# orienteringsklokke_v3.net
KiCad netlist of a schematic drawn in EAGLE
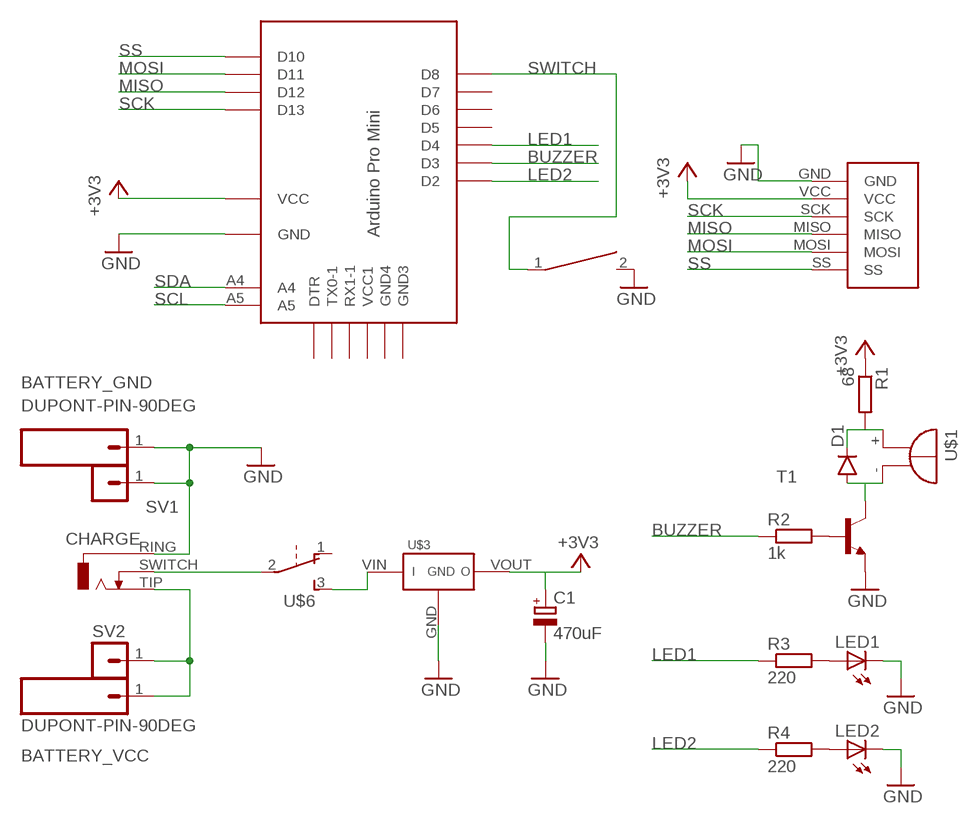
[diagram p0: schematic, sheet 1]

(export (version "E")
  (design (tool "Eeschema 10.0.6"))
  (components
    (comp (ref "BATTERY_GND")
      (value "DUPONT-PIN-90DEG")
      (footprint "eagle-import:DUPONT-PIN-90DEG")
      (libsource (lib "eagle-import") (part "DUPONT-PIN-90DEG"))
    )
    (comp (ref "BATTERY_VCC")
      (value "DUPONT-PIN-90DEG")
      (footprint "eagle-import:DUPONT-PIN-90DEG")
      (libsource (lib "eagle-import") (part "DUPONT-PIN-90DEG"))
    )
    (comp (ref "C1")
      (value "470uF")
      (footprint "eagle-import:CAP-HORIZ-6.5X11X2.5")
      (libsource (lib "eagle-import") (part "CAP-HORIZ"))
    )
    (comp (ref "CHARGE")
      (value "ST613-JACK")
      (footprint "eagle-import:ST613-JACK")
      (libsource (lib "eagle-import") (part "ST613-JACK"))
    )
    (comp (ref "D1")
      (value "1N4148DOJ35-5")
      (footprint "eagle-import:DO35-5J")
      (libsource (lib "eagle-import") (part "1N4148DOJ35-5"))
    )
    (comp (ref "LED1")
      (value "LED_J3MM-LEFT")
      (footprint "eagle-import:LED90DEG_LEFT")
      (libsource (lib "eagle-import") (part "LED_J3MM-LEFT"))
    )
    (comp (ref "LED2")
      (value "LED_J3MM-LEFT")
      (footprint "eagle-import:LED90DEG_LEFT")
      (libsource (lib "eagle-import") (part "LED_J3MM-LEFT"))
    )
    (comp (ref "R1")
      (value "68")
      (footprint "eagle-import:0204_5")
      (libsource (lib "eagle-import") (part "R-EU_0204/5"))
    )
    (comp (ref "R2")
      (value "1k")
      (footprint "eagle-import:0204_5")
      (libsource (lib "eagle-import") (part "R-EU_0204/5"))
    )
    (comp (ref "R3")
      (value "220")
      (footprint "eagle-import:0204_5")
      (libsource (lib "eagle-import") (part "R-EU_0204/5"))
    )
    (comp (ref "R4")
      (value "220")
      (footprint "eagle-import:0204_5")
      (libsource (lib "eagle-import") (part "R-EU_0204/5"))
    )
    (comp (ref "SV1")
      (value "MA01-1JC")
      (footprint "eagle-import:MA01-1J")
      (libsource (lib "eagle-import") (part "MA01-1JC"))
    )
    (comp (ref "SV2")
      (value "MA01-1JC")
      (footprint "eagle-import:MA01-1J")
      (libsource (lib "eagle-import") (part "MA01-1JC"))
    )
    (comp (ref "T1")
      (value "2N3904-NPN-TO92-EBC")
      (footprint "eagle-import:TO92-EBC")
      (libsource (lib "eagle-import") (part "-NPN-TO92-EBC2N3904"))
    )
    (comp (ref "U$1")
      (value "BUZZER_JL")
      (footprint "eagle-import:BUZZER_HORIZ_J_LEFT")
      (libsource (lib "eagle-import") (part "BUZZER_JL"))
    )
    (comp (ref "U$2")
      (value "NFC_MODULE_V3_SPINH")
      (footprint "eagle-import:NFC_MODULE_V3_SPI_CENTERED_NO_HOLES")
      (libsource (lib "eagle-import") (part "NFC_MODULE_V3_SPINH"))
    )
    (comp (ref "U$3")
      (value "VOLT_BOOST")
      (footprint "eagle-import:VOLT-BOOST")
      (libsource (lib "eagle-import") (part "VOLT_BOOST"))
    )
    (comp (ref "U$4")
      (value "ARD-PRO-MINI-ORIENTERING")
      (footprint "eagle-import:ARD_PRO_MINI_ORIENTERING")
      (libsource (lib "eagle-import") (part "ARD-PRO-MINI-ORIENTERING"))
    )
    (comp (ref "U$5")
      (value "PUSHBUTTON_2P6MM")
      (footprint "eagle-import:PUSHBUTTON_HORIZ_6MM_J")
      (libsource (lib "eagle-import") (part "PUSHBUTTON_2P6MM"))
    )
    (comp (ref "U$6")
      (value "SK12D07-SLIDE-SWITCH")
      (footprint "eagle-import:SK12D07")
      (libsource (lib "eagle-import") (part "SK12D07-SLIDE-SWITCH"))
    )
  )
  (nets
    (net (code "1") (name "+3V3") (class "Default")
      (node (ref "C1") (pin "+") (pinfunction "+_+") (pintype "passive"))
      (node (ref "R1") (pin "1") (pinfunction "1_1") (pintype "passive"))
      (node (ref "U$2") (pin "VCC") (pinfunction "VCC_VCC") (pintype "bidirectional"))
      (node (ref "U$3") (pin "VOUT") (pinfunction "VOUT_VOUT") (pintype "bidirectional"))
      (node (ref "U$4") (pin "VCC") (pinfunction "VCC_VCC") (pintype "bidirectional"))
    )
    (net (code "2") (name "BUZZER") (class "Default")
      (node (ref "R2") (pin "1") (pinfunction "1_1") (pintype "passive"))
      (node (ref "U$4") (pin "D3") (pinfunction "D3_D3") (pintype "bidirectional"))
    )
    (net (code "3") (name "GND") (class "Default")
      (node (ref "BATTERY_GND") (pin "1") (pinfunction "1_1") (pintype "passive"))
      (node (ref "C1") (pin "-") (pinfunction "-_-") (pintype "passive"))
      (node (ref "CHARGE") (pin "RING") (pinfunction "1_RING") (pintype "passive"))
      (node (ref "LED1") (pin "K") (pinfunction "C_K") (pintype "passive"))
      (node (ref "LED2") (pin "K") (pinfunction "C_K") (pintype "passive"))
      (node (ref "SV1") (pin "1") (pinfunction "1_1") (pintype "passive"))
      (node (ref "T1") (pin "E") (pinfunction "E_E") (pintype "passive"))
      (node (ref "U$2") (pin "GND") (pinfunction "GND_GND") (pintype "bidirectional"))
      (node (ref "U$3") (pin "GND") (pinfunction "GND_GND") (pintype "bidirectional"))
      (node (ref "U$4") (pin "GND") (pinfunction "GND_GND") (pintype "bidirectional"))
      (node (ref "U$5") (pin "2") (pinfunction "2_2") (pintype "bidirectional"))
    )
    (net (code "4") (name "LED1") (class "Default")
      (node (ref "R3") (pin "1") (pinfunction "1_1") (pintype "passive"))
      (node (ref "U$4") (pin "D4") (pinfunction "D4_D4") (pintype "bidirectional"))
    )
    (net (code "5") (name "LED2") (class "Default")
      (node (ref "R4") (pin "1") (pinfunction "1_1") (pintype "passive"))
      (node (ref "U$4") (pin "D2") (pinfunction "D2_D2") (pintype "bidirectional"))
    )
    (net (code "6") (name "MISO") (class "Default")
      (node (ref "U$2") (pin "MISO") (pinfunction "MISO_MISO") (pintype "bidirectional"))
      (node (ref "U$4") (pin "D12") (pinfunction "D12_D12") (pintype "bidirectional"))
    )
    (net (code "7") (name "MOSI") (class "Default")
      (node (ref "U$2") (pin "MOSI") (pinfunction "MOSI_MOSI") (pintype "bidirectional"))
      (node (ref "U$4") (pin "D11") (pinfunction "D11_D11") (pintype "bidirectional"))
    )
    (net (code "8") (name "Net-(CHARGE-2)") (class "Default")
      (node (ref "CHARGE") (pin "SWITCH") (pinfunction "2_SWITCH") (pintype "passive"))
      (node (ref "U$6") (pin "2") (pinfunction "2_2") (pintype "passive"))
    )
    (net (code "9") (name "Net-(CHARGE-3)") (class "Default")
      (node (ref "BATTERY_VCC") (pin "1") (pinfunction "1_1") (pintype "passive"))
      (node (ref "CHARGE") (pin "TIP") (pinfunction "3_TIP") (pintype "passive"))
      (node (ref "SV2") (pin "1") (pinfunction "1_1") (pintype "passive"))
    )
    (net (code "10") (name "Net-(D1-PadA)") (class "Default")
      (node (ref "D1") (pin "A") (pinfunction "A_A") (pintype "passive"))
      (node (ref "T1") (pin "C") (pinfunction "C_C") (pintype "passive"))
      (node (ref "U$1") (pin "-") (pinfunction "-_-") (pintype "passive"))
    )
    (net (code "11") (name "Net-(D1-PadC)") (class "Default")
      (node (ref "D1") (pin "C") (pinfunction "C_C") (pintype "passive"))
      (node (ref "R1") (pin "2") (pinfunction "2_2") (pintype "passive"))
      (node (ref "U$1") (pin "+") (pinfunction "+_+") (pintype "passive"))
    )
    (net (code "12") (name "Net-(LED1-PadA)") (class "Default")
      (node (ref "LED1") (pin "A") (pinfunction "A_A") (pintype "passive"))
      (node (ref "R3") (pin "2") (pinfunction "2_2") (pintype "passive"))
    )
    (net (code "13") (name "Net-(LED2-PadA)") (class "Default")
      (node (ref "LED2") (pin "A") (pinfunction "A_A") (pintype "passive"))
      (node (ref "R4") (pin "2") (pinfunction "2_2") (pintype "passive"))
    )
    (net (code "14") (name "Net-(R2-Pad2)") (class "Default")
      (node (ref "R2") (pin "2") (pinfunction "2_2") (pintype "passive"))
      (node (ref "T1") (pin "B") (pinfunction "B_B") (pintype "passive"))
    )
    (net (code "15") (name "Net-(U$3-PadVIN)") (class "Default")
      (node (ref "U$3") (pin "VIN") (pinfunction "VIN_VIN") (pintype "bidirectional"))
      (node (ref "U$6") (pin "3") (pinfunction "3_3") (pintype "passive"))
    )
    (net (code "16") (name "SCK") (class "Default")
      (node (ref "U$2") (pin "SCK") (pinfunction "SCK_SCK") (pintype "bidirectional"))
      (node (ref "U$4") (pin "D13") (pinfunction "D13_D13") (pintype "bidirectional"))
    )
    (net (code "17") (name "SCL") (class "Default")
      (node (ref "U$4") (pin "A5") (pinfunction "A5_A5") (pintype "bidirectional"))
    )
    (net (code "18") (name "SDA") (class "Default")
      (node (ref "U$4") (pin "A4") (pinfunction "A4_A4") (pintype "bidirectional"))
    )
    (net (code "19") (name "SS") (class "Default")
      (node (ref "U$2") (pin "SS") (pinfunction "SS_SS") (pintype "bidirectional"))
      (node (ref "U$4") (pin "D10") (pinfunction "D10_D10") (pintype "bidirectional"))
    )
    (net (code "20") (name "SWITCH") (class "Default")
      (node (ref "U$4") (pin "D8") (pinfunction "D8_D8") (pintype "bidirectional"))
      (node (ref "U$5") (pin "1") (pinfunction "1_1") (pintype "bidirectional"))
    )
    (net (code "21") (name "unconnected-(U$4-GND3-PadGND2)") (class "Default")
      (node (ref "U$4") (pin "GND2") (pinfunction "GND3_GND2") (pintype "bidirectional"))
    )
    (net (code "22") (name "unconnected-(U$4-GND4-PadGND3)") (class "Default")
      (node (ref "U$4") (pin "GND3") (pinfunction "GND4_GND3") (pintype "bidirectional"))
    )
    (net (code "23") (name "unconnected-(U$4-PadD5)") (class "Default")
      (node (ref "U$4") (pin "D5") (pinfunction "D5_D5") (pintype "bidirectional"))
    )
    (net (code "24") (name "unconnected-(U$4-PadD6)") (class "Default")
      (node (ref "U$4") (pin "D6") (pinfunction "D6_D6") (pintype "bidirectional"))
    )
    (net (code "25") (name "unconnected-(U$4-PadD7)") (class "Default")
      (node (ref "U$4") (pin "D7") (pinfunction "D7_D7") (pintype "bidirectional"))
    )
    (net (code "26") (name "unconnected-(U$4-PadDTR)") (class "Default")
      (node (ref "U$4") (pin "DTR") (pinfunction "DTR_DTR") (pintype "bidirectional"))
    )
    (net (code "27") (name "unconnected-(U$4-PadRX1-1)") (class "Default")
      (node (ref "U$4") (pin "RX1-1") (pinfunction "RX1-1_RX1-1") (pintype "bidirectional"))
    )
    (net (code "28") (name "unconnected-(U$4-PadTX0-1)") (class "Default")
      (node (ref "U$4") (pin "TX0-1") (pinfunction "TX0-1_TX0-1") (pintype "bidirectional"))
    )
    (net (code "29") (name "unconnected-(U$4-PadVCC1)") (class "Default")
      (node (ref "U$4") (pin "VCC1") (pinfunction "VCC1_VCC1") (pintype "bidirectional"))
    )
    (net (code "30") (name "unconnected-(U$6-Pad1)") (class "Default")
      (node (ref "U$6") (pin "1") (pinfunction "1_1") (pintype "passive"))
    )
  )
)
